# UpTo11_FrontPanel.net
KiCad netlist of a schematic drawn in EAGLE
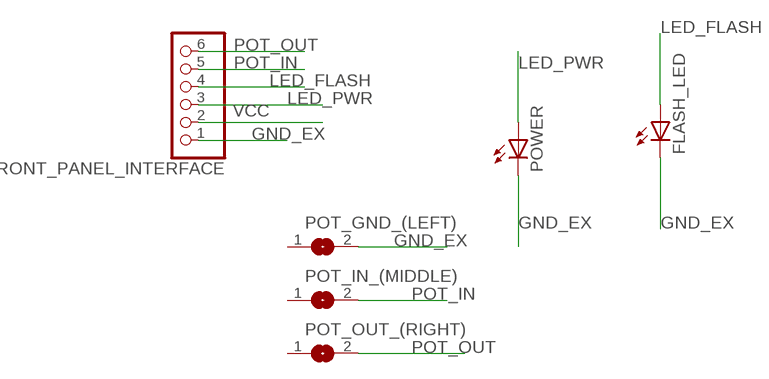
[diagram p0: schematic, sheet 1]

(export (version "E")
  (design (tool "Eeschema 10.0.6"))
  (components
    (comp (ref "FLASH_LED")
      (value "LED5MM")
      (footprint "eagle-import:LED5MM")
      (libsource (lib "eagle-import") (part "LED5MM"))
    )
    (comp (ref "FRONT_PANEL_INTERFACE")
      (value "PINHD-1X6")
      (footprint "eagle-import:1X06")
      (libsource (lib "eagle-import") (part "PINHD-1X6"))
    )
    (comp (ref "POT_GND_(LEFT)")
      (value "SOLDERJUMPERREFLOW")
      (footprint "eagle-import:SOLDERJUMPER_REFLOW")
      (libsource (lib "eagle-import") (part "SOLDERJUMPERREFLOW"))
    )
    (comp (ref "POT_IN_(MIDDLE)")
      (value "SOLDERJUMPERREFLOW")
      (footprint "eagle-import:SOLDERJUMPER_REFLOW")
      (libsource (lib "eagle-import") (part "SOLDERJUMPERREFLOW"))
    )
    (comp (ref "POT_OUT_(RIGHT)")
      (value "SOLDERJUMPERREFLOW")
      (footprint "eagle-import:SOLDERJUMPER_REFLOW")
      (libsource (lib "eagle-import") (part "SOLDERJUMPERREFLOW"))
    )
    (comp (ref "POWER")
      (value "LEDSMT1206")
      (footprint "eagle-import:1206")
      (libsource (lib "eagle-import") (part "LEDSMT1206"))
    )
  )
  (nets
    (net (code "1") (name "/GND_EX") (class "Default")
      (node (ref "FLASH_LED") (pin "K") (pinfunction "C_K") (pintype "passive"))
      (node (ref "FRONT_PANEL_INTERFACE") (pin "1") (pinfunction "1_1") (pintype "passive"))
      (node (ref "POT_GND_(LEFT)") (pin "2") (pinfunction "2_2") (pintype "passive"))
      (node (ref "POWER") (pin "C") (pinfunction "C_C") (pintype "passive"))
    )
    (net (code "2") (name "/LED_FLASH") (class "Default")
      (node (ref "FLASH_LED") (pin "A") (pinfunction "A_A") (pintype "passive"))
      (node (ref "FRONT_PANEL_INTERFACE") (pin "4") (pinfunction "4_4") (pintype "passive"))
    )
    (net (code "3") (name "/LED_PWR") (class "Default")
      (node (ref "FRONT_PANEL_INTERFACE") (pin "3") (pinfunction "3_3") (pintype "passive"))
      (node (ref "POWER") (pin "A") (pinfunction "A_A") (pintype "passive"))
    )
    (net (code "4") (name "/POT_IN") (class "Default")
      (node (ref "FRONT_PANEL_INTERFACE") (pin "5") (pinfunction "5_5") (pintype "passive"))
      (node (ref "POT_IN_(MIDDLE)") (pin "2") (pinfunction "2_2") (pintype "passive"))
    )
    (net (code "5") (name "/POT_OUT") (class "Default")
      (node (ref "FRONT_PANEL_INTERFACE") (pin "6") (pinfunction "6_6") (pintype "passive"))
      (node (ref "POT_OUT_(RIGHT)") (pin "2") (pinfunction "2_2") (pintype "passive"))
    )
    (net (code "6") (name "/VCC") (class "Default")
      (node (ref "FRONT_PANEL_INTERFACE") (pin "2") (pinfunction "2_2") (pintype "passive"))
    )
    (net (code "7") (name "unconnected-(POT_GND_(LEFT)-Pad1)") (class "Default")
      (node (ref "POT_GND_(LEFT)") (pin "1") (pinfunction "1_1") (pintype "passive"))
    )
    (net (code "8") (name "unconnected-(POT_IN_(MIDDLE)-Pad1)") (class "Default")
      (node (ref "POT_IN_(MIDDLE)") (pin "1") (pinfunction "1_1") (pintype "passive"))
    )
    (net (code "9") (name "unconnected-(POT_OUT_(RIGHT)-Pad1)") (class "Default")
      (node (ref "POT_OUT_(RIGHT)") (pin "1") (pinfunction "1_1") (pintype "passive"))
    )
  )
)
